# 19_WIFI_BLE.net
KiCad netlist of a schematic drawn in Altium Designer
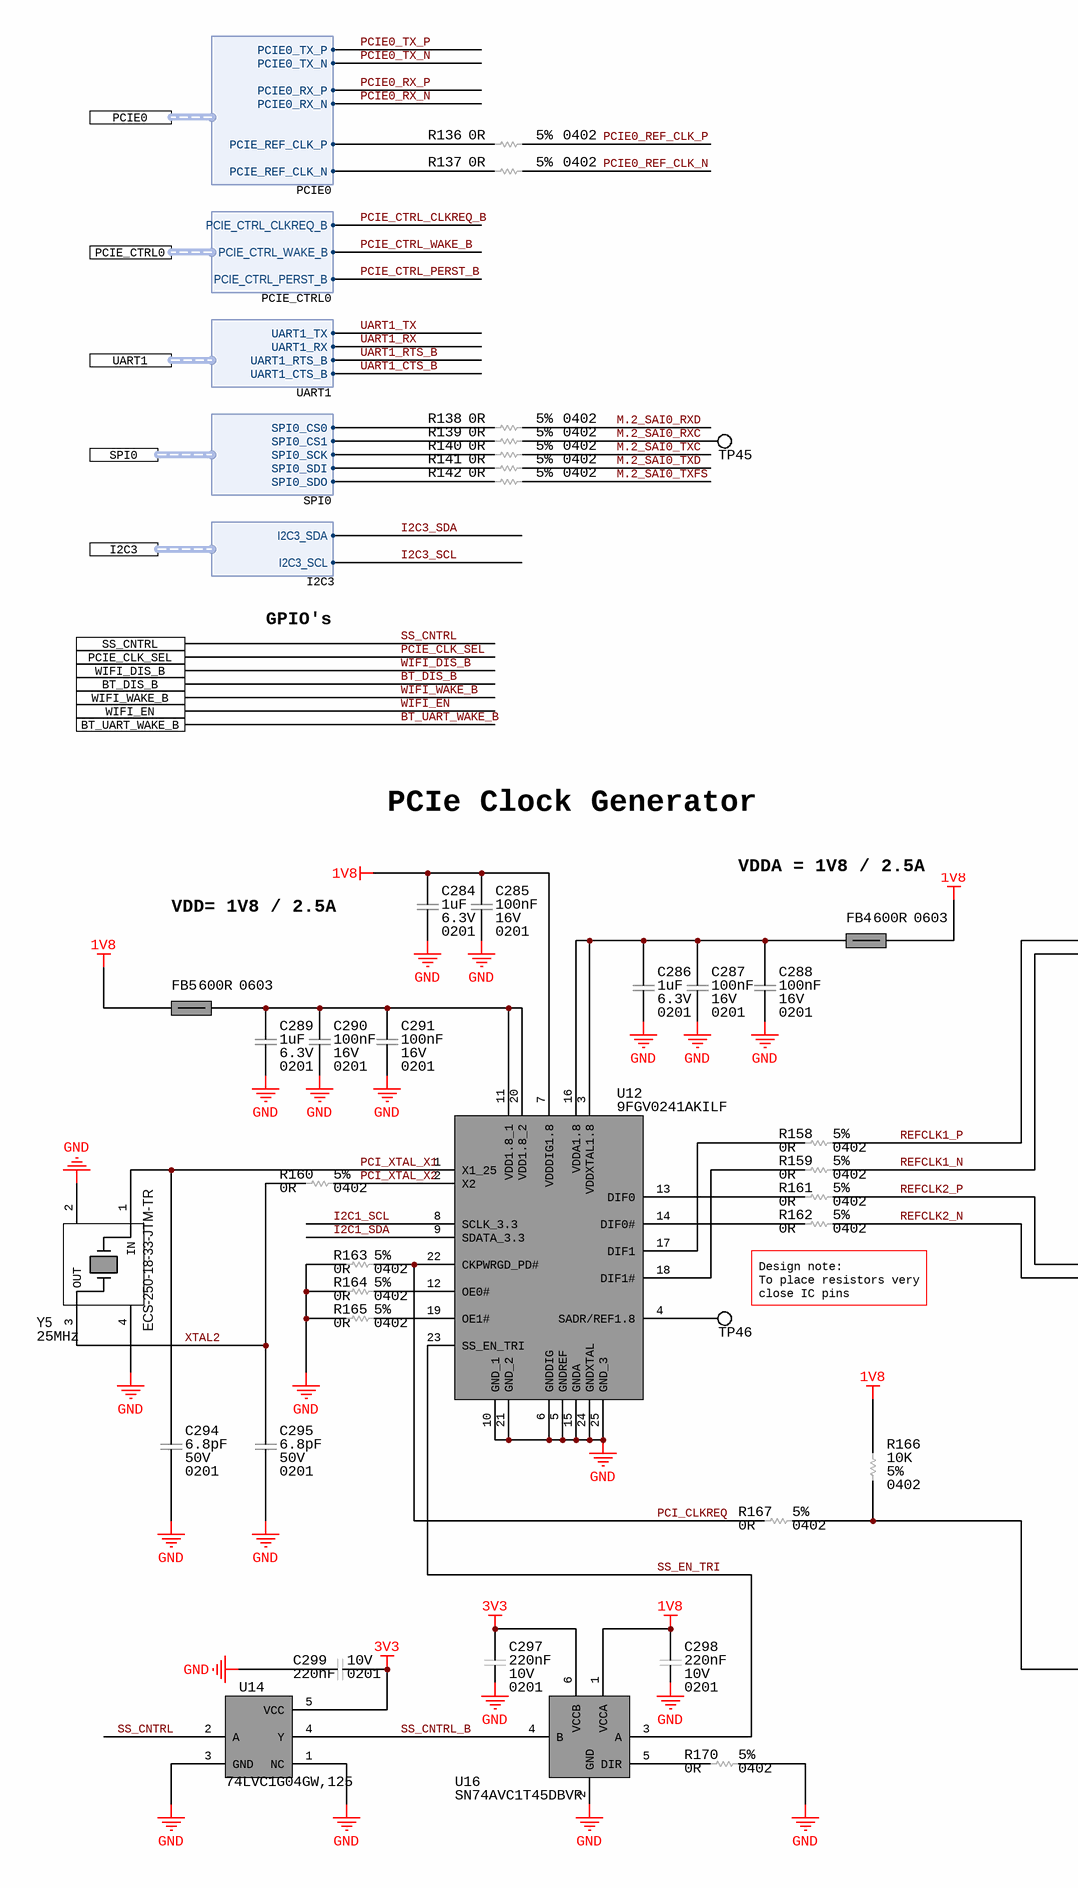
[diagram p0: 19_WIFI_BLE.SchDoc, left]
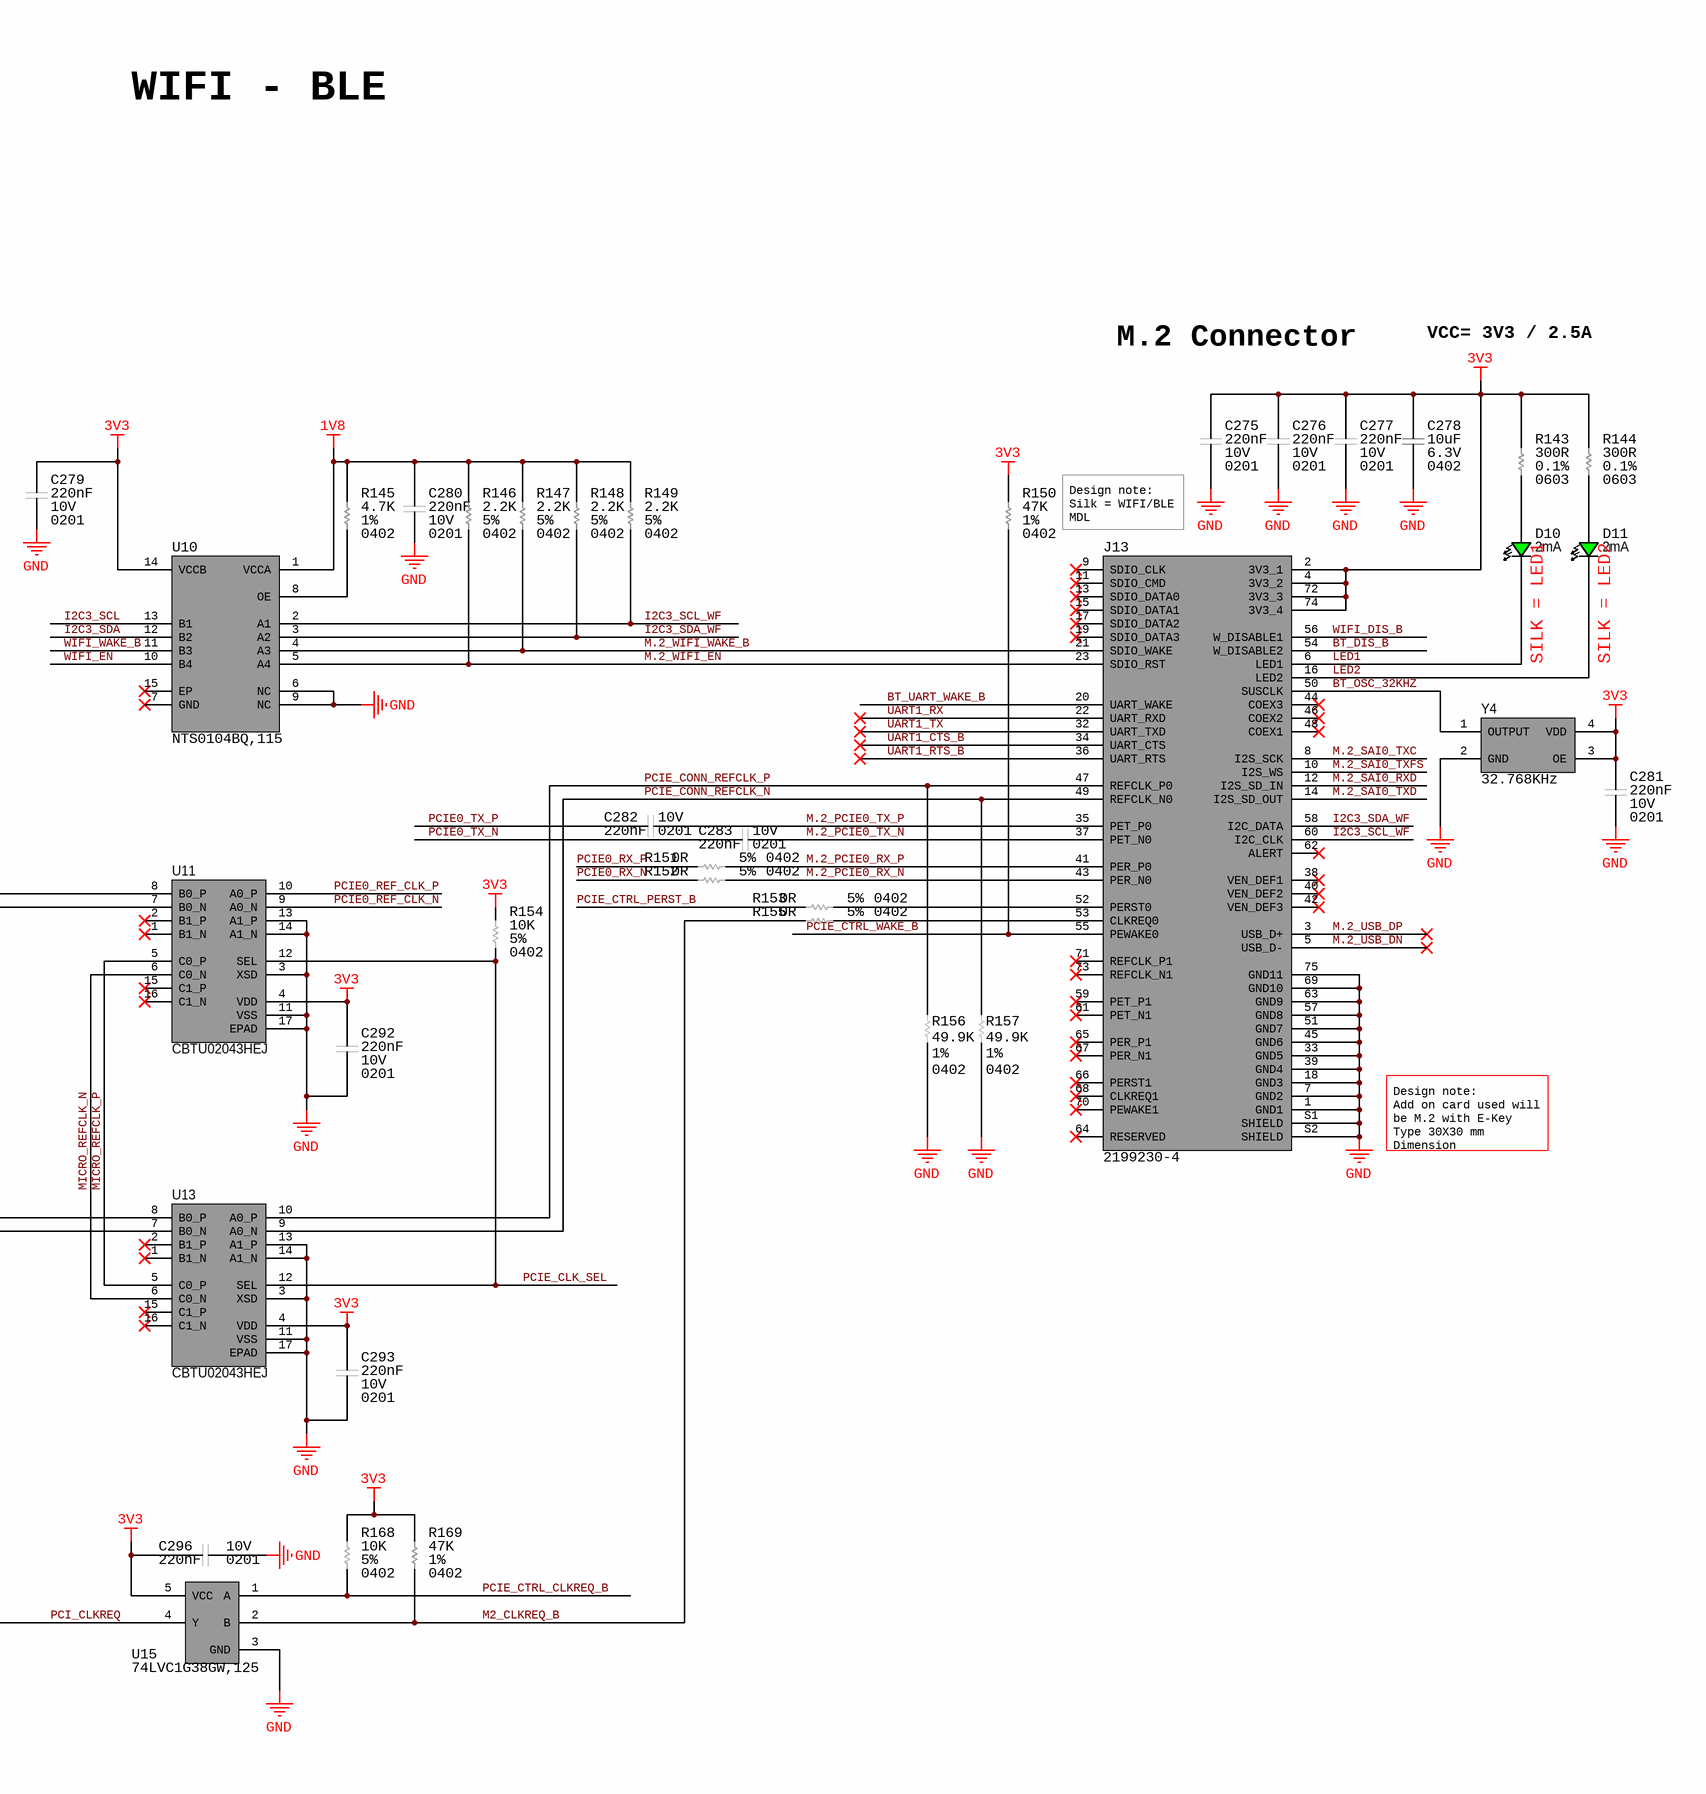
[diagram p1: 19_WIFI_BLE.SchDoc, right]

(export (version "E")
  (design (tool "Eeschema 10.0.6"))
  (components
    (comp (ref "C275")
      (value "LMK063BJ224MP-F")
      (footprint "CAP_0201_CAPC0603X03N")
      (description "Multilayer Ceramic Capacitors (High dielectric type), 10V, 0.22 uF, ± 20 %, 0201, X5R, RoHS")
      (fields
        (field (name "MANUFACTURER") "Taiyo Yuden")
        (field (name "TOLERANCE") "20%")
        (field (name "VOLTAGE RATING (DC)") "10V")
        (field (name "CAPACITANCE") "220nF")
        (field (name "CASE/PACKAGE") "0201")
      )
      (libsource (lib "Electronic Devices_LIB") (part "CAP_0.22UF_10V_X5R_0201"))
    )
    (comp (ref "C276")
      (value "LMK063BJ224MP-F")
      (footprint "CAP_0201_CAPC0603X03N")
      (description "Multilayer Ceramic Capacitors (High dielectric type), 10V, 0.22 uF, ± 20 %, 0201, X5R, RoHS")
      (fields
        (field (name "MANUFACTURER") "Taiyo Yuden")
        (field (name "TOLERANCE") "20%")
        (field (name "VOLTAGE RATING (DC)") "10V")
        (field (name "CAPACITANCE") "220nF")
        (field (name "CASE/PACKAGE") "0201")
      )
      (libsource (lib "Electronic Devices_LIB") (part "CAP_0.22UF_10V_X5R_0201"))
    )
    (comp (ref "C277")
      (value "LMK063BJ224MP-F")
      (footprint "CAP_0201_CAPC0603X03N")
      (description "Multilayer Ceramic Capacitors (High dielectric type), 10V, 0.22 uF, ± 20 %, 0201, X5R, RoHS")
      (fields
        (field (name "MANUFACTURER") "Taiyo Yuden")
        (field (name "TOLERANCE") "20%")
        (field (name "VOLTAGE RATING (DC)") "10V")
        (field (name "CAPACITANCE") "220nF")
        (field (name "CASE/PACKAGE") "0201")
      )
      (libsource (lib "Electronic Devices_LIB") (part "CAP_0.22UF_10V_X5R_0201"))
    )
    (comp (ref "C278")
      (value "CL05A106MQ5NUNC")
      (footprint "CAP_0402_CAPC1005X05N")
      (description "Cap Ceramic 10uF 6.3V X5R 20% SMD 0402 85C T/R")
      (fields
        (field (name "MANUFACTURER") "Samsung")
        (field (name "TOLERANCE") "20%")
        (field (name "CASE/PACKAGE") "0402")
        (field (name "CAPACITANCE") "10uF")
        (field (name "VOLTAGE RATING") "6.3V")
      )
      (libsource (lib "Electronic Devices_LIB") (part "CAP_10UF_6.3V_X5R_0402"))
    )
    (comp (ref "C279")
      (value "LMK063BJ224MP-F")
      (footprint "CAP_0201_CAPC0603X03N")
      (description "Multilayer Ceramic Capacitors (High dielectric type), 10V, 0.22 uF, ± 20 %, 0201, X5R, RoHS")
      (fields
        (field (name "MANUFACTURER") "Taiyo Yuden")
        (field (name "TOLERANCE") "20%")
        (field (name "VOLTAGE RATING (DC)") "10V")
        (field (name "CAPACITANCE") "220nF")
        (field (name "CASE/PACKAGE") "0201")
      )
      (libsource (lib "Electronic Devices_LIB") (part "CAP_0.22UF_10V_X5R_0201"))
    )
    (comp (ref "C280")
      (value "LMK063BJ224MP-F")
      (footprint "CAP_0201_CAPC0603X03N")
      (description "Multilayer Ceramic Capacitors (High dielectric type), 10V, 0.22 uF, ± 20 %, 0201, X5R, RoHS")
      (fields
        (field (name "MANUFACTURER") "Taiyo Yuden")
        (field (name "TOLERANCE") "20%")
        (field (name "VOLTAGE RATING (DC)") "10V")
        (field (name "CAPACITANCE") "220nF")
        (field (name "CASE/PACKAGE") "0201")
      )
      (libsource (lib "Electronic Devices_LIB") (part "CAP_0.22UF_10V_X5R_0201"))
    )
    (comp (ref "C281")
      (value "LMK063BJ224MP-F")
      (footprint "CAP_0201_CAPC0603X03N")
      (description "Multilayer Ceramic Capacitors (High dielectric type), 10V, 0.22 uF, ± 20 %, 0201, X5R, RoHS")
      (fields
        (field (name "MANUFACTURER") "Taiyo Yuden")
        (field (name "TOLERANCE") "20%")
        (field (name "VOLTAGE RATING (DC)") "10V")
        (field (name "CAPACITANCE") "220nF")
        (field (name "CASE/PACKAGE") "0201")
      )
      (libsource (lib "Electronic Devices_LIB") (part "CAP_0.22UF_10V_X5R_0201"))
    )
    (comp (ref "C282")
      (value "LMK063BJ224MP-F")
      (footprint "CAP_0201_CAPC0603X03N")
      (description "Multilayer Ceramic Capacitors (High dielectric type), 10V, 0.22 uF, ± 20 %, 0201, X5R, RoHS")
      (fields
        (field (name "MANUFACTURER") "Taiyo Yuden")
        (field (name "TOLERANCE") "20%")
        (field (name "VOLTAGE RATING (DC)") "10V")
        (field (name "CAPACITANCE") "220nF")
        (field (name "CASE/PACKAGE") "0201")
      )
      (libsource (lib "Electronic Devices_LIB") (part "CAP_0.22UF_10V_X5R_0201"))
    )
    (comp (ref "C283")
      (value "LMK063BJ224MP-F")
      (footprint "CAP_0201_CAPC0603X03N")
      (description "Multilayer Ceramic Capacitors (High dielectric type), 10V, 0.22 uF, ± 20 %, 0201, X5R, RoHS")
      (fields
        (field (name "MANUFACTURER") "Taiyo Yuden")
        (field (name "TOLERANCE") "20%")
        (field (name "VOLTAGE RATING (DC)") "10V")
        (field (name "CAPACITANCE") "220nF")
        (field (name "CASE/PACKAGE") "0201")
      )
      (libsource (lib "Electronic Devices_LIB") (part "CAP_0.22UF_10V_X5R_0201"))
    )
    (comp (ref "C284")
      (value "02016D105MAT2A")
      (footprint "CAP_0201_CAPC0603X03N")
      (description "0201 1 uF 6.3 V ±20 % Tolerance X5R Surface Mount Multilayer Ceramic Capacitor")
      (fields
        (field (name "MANUFACTURER") "Kyocera AVX")
        (field (name "TOLERANCE") "20%")
        (field (name "VOLTAGE RATING (DC)") "6.3V")
        (field (name "CAPACITANCE") "1uF")
        (field (name "CASE/PACKAGE") "0201")
      )
      (libsource (lib "Electronic Devices_LIB") (part "CAP_1UF_6.3V_X5R_0201"))
    )
    (comp (ref "C285")
      (value "GRM033C71C104KE14D")
      (footprint "CAP_0201_CAPC0603X03N")
      (description "Multilayer Ceramic Capacitor, 0.1 uF, 16 V, ± 10%, X7S, 0201 [0603 Metric]")
      (fields
        (field (name "MANUFACTURER") "Murata")
        (field (name "TOLERANCE") "10%")
        (field (name "VOLTAGE RATING") "16V")
        (field (name "CAPACITANCE") "100nF")
        (field (name "CASE/PACKAGE") "0201")
      )
      (libsource (lib "Electronic Devices_LIB") (part "CAP_100nF_16V_X7S_0201"))
    )
    (comp (ref "C286")
      (value "02016D105MAT2A")
      (footprint "CAP_0201_CAPC0603X03N")
      (description "0201 1 uF 6.3 V ±20 % Tolerance X5R Surface Mount Multilayer Ceramic Capacitor")
      (fields
        (field (name "MANUFACTURER") "Kyocera AVX")
        (field (name "TOLERANCE") "20%")
        (field (name "VOLTAGE RATING (DC)") "6.3V")
        (field (name "CAPACITANCE") "1uF")
        (field (name "CASE/PACKAGE") "0201")
      )
      (libsource (lib "Electronic Devices_LIB") (part "CAP_1UF_6.3V_X5R_0201"))
    )
    (comp (ref "C287")
      (value "GRM033C71C104KE14D")
      (footprint "CAP_0201_CAPC0603X03N")
      (description "Multilayer Ceramic Capacitor, 0.1 uF, 16 V, ± 10%, X7S, 0201 [0603 Metric]")
      (fields
        (field (name "MANUFACTURER") "Murata")
        (field (name "TOLERANCE") "10%")
        (field (name "VOLTAGE RATING") "16V")
        (field (name "CAPACITANCE") "100nF")
        (field (name "CASE/PACKAGE") "0201")
      )
      (libsource (lib "Electronic Devices_LIB") (part "CAP_100nF_16V_X7S_0201"))
    )
    (comp (ref "C288")
      (value "GRM033C71C104KE14D")
      (footprint "CAP_0201_CAPC0603X03N")
      (description "Multilayer Ceramic Capacitor, 0.1 uF, 16 V, ± 10%, X7S, 0201 [0603 Metric]")
      (fields
        (field (name "MANUFACTURER") "Murata")
        (field (name "TOLERANCE") "10%")
        (field (name "VOLTAGE RATING") "16V")
        (field (name "CAPACITANCE") "100nF")
        (field (name "CASE/PACKAGE") "0201")
      )
      (libsource (lib "Electronic Devices_LIB") (part "CAP_100nF_16V_X7S_0201"))
    )
    (comp (ref "C289")
      (value "02016D105MAT2A")
      (footprint "CAP_0201_CAPC0603X03N")
      (description "0201 1 uF 6.3 V ±20 % Tolerance X5R Surface Mount Multilayer Ceramic Capacitor")
      (fields
        (field (name "MANUFACTURER") "Kyocera AVX")
        (field (name "TOLERANCE") "20%")
        (field (name "VOLTAGE RATING (DC)") "6.3V")
        (field (name "CAPACITANCE") "1uF")
        (field (name "CASE/PACKAGE") "0201")
      )
      (libsource (lib "Electronic Devices_LIB") (part "CAP_1UF_6.3V_X5R_0201"))
    )
    (comp (ref "C290")
      (value "GRM033C71C104KE14D")
      (footprint "CAP_0201_CAPC0603X03N")
      (description "Multilayer Ceramic Capacitor, 0.1 uF, 16 V, ± 10%, X7S, 0201 [0603 Metric]")
      (fields
        (field (name "MANUFACTURER") "Murata")
        (field (name "TOLERANCE") "10%")
        (field (name "VOLTAGE RATING") "16V")
        (field (name "CAPACITANCE") "100nF")
        (field (name "CASE/PACKAGE") "0201")
      )
      (libsource (lib "Electronic Devices_LIB") (part "CAP_100nF_16V_X7S_0201"))
    )
    (comp (ref "C291")
      (value "GRM033C71C104KE14D")
      (footprint "CAP_0201_CAPC0603X03N")
      (description "Multilayer Ceramic Capacitor, 0.1 uF, 16 V, ± 10%, X7S, 0201 [0603 Metric]")
      (fields
        (field (name "MANUFACTURER") "Murata")
        (field (name "TOLERANCE") "10%")
        (field (name "VOLTAGE RATING") "16V")
        (field (name "CAPACITANCE") "100nF")
        (field (name "CASE/PACKAGE") "0201")
      )
      (libsource (lib "Electronic Devices_LIB") (part "CAP_100nF_16V_X7S_0201"))
    )
    (comp (ref "C292")
      (value "LMK063BJ224MP-F")
      (footprint "CAP_0201_CAPC0603X03N")
      (description "Multilayer Ceramic Capacitors (High dielectric type), 10V, 0.22 uF, ± 20 %, 0201, X5R, RoHS")
      (fields
        (field (name "MANUFACTURER") "Taiyo Yuden")
        (field (name "TOLERANCE") "20%")
        (field (name "VOLTAGE RATING (DC)") "10V")
        (field (name "CAPACITANCE") "220nF")
        (field (name "CASE/PACKAGE") "0201")
      )
      (libsource (lib "Electronic Devices_LIB") (part "CAP_0.22UF_10V_X5R_0201"))
    )
    (comp (ref "C293")
      (value "LMK063BJ224MP-F")
      (footprint "CAP_0201_CAPC0603X03N")
      (description "Multilayer Ceramic Capacitors (High dielectric type), 10V, 0.22 uF, ± 20 %, 0201, X5R, RoHS")
      (fields
        (field (name "MANUFACTURER") "Taiyo Yuden")
        (field (name "TOLERANCE") "20%")
        (field (name "VOLTAGE RATING (DC)") "10V")
        (field (name "CAPACITANCE") "220nF")
        (field (name "CASE/PACKAGE") "0201")
      )
      (libsource (lib "Electronic Devices_LIB") (part "CAP_0.22UF_10V_X5R_0201"))
    )
    (comp (ref "C294")
      (value "GRM0335C1H6R8BA01D")
      (footprint "CAP_0201_CAPC0603X03N")
      (description "Cap Ceramic 6.8pF 50V C0G 0.1pF Pad SMD 0201 125C T/R")
      (fields
        (field (name "MANUFACTURER") "Murata")
        (field (name "CAPACITANCE") "6.8pF")
        (field (name "VOLTAGE RATING") "50V")
        (field (name "CASE/PACKAGE") "0201")
      )
      (libsource (lib "Electronic Devices_LIB") (part "CAP_6.8pF_50V_NP0_0201"))
    )
    (comp (ref "C295")
      (value "GRM0335C1H6R8BA01D")
      (footprint "CAP_0201_CAPC0603X03N")
      (description "Cap Ceramic 6.8pF 50V C0G 0.1pF Pad SMD 0201 125C T/R")
      (fields
        (field (name "MANUFACTURER") "Murata")
        (field (name "CAPACITANCE") "6.8pF")
        (field (name "VOLTAGE RATING") "50V")
        (field (name "CASE/PACKAGE") "0201")
      )
      (libsource (lib "Electronic Devices_LIB") (part "CAP_6.8pF_50V_NP0_0201"))
    )
    (comp (ref "C296")
      (value "LMK063BJ224MP-F")
      (footprint "CAP_0201_CAPC0603X03N")
      (description "Multilayer Ceramic Capacitors (High dielectric type), 10V, 0.22 uF, ± 20 %, 0201, X5R, RoHS")
      (fields
        (field (name "MANUFACTURER") "Taiyo Yuden")
        (field (name "TOLERANCE") "20%")
        (field (name "VOLTAGE RATING (DC)") "10V")
        (field (name "CAPACITANCE") "220nF")
        (field (name "CASE/PACKAGE") "0201")
      )
      (libsource (lib "Electronic Devices_LIB") (part "CAP_0.22UF_10V_X5R_0201"))
    )
    (comp (ref "C297")
      (value "LMK063BJ224MP-F")
      (footprint "CAP_0201_CAPC0603X03N")
      (description "Multilayer Ceramic Capacitors (High dielectric type), 10V, 0.22 uF, ± 20 %, 0201, X5R, RoHS")
      (fields
        (field (name "MANUFACTURER") "Taiyo Yuden")
        (field (name "TOLERANCE") "20%")
        (field (name "VOLTAGE RATING (DC)") "10V")
        (field (name "CAPACITANCE") "220nF")
        (field (name "CASE/PACKAGE") "0201")
      )
      (libsource (lib "Electronic Devices_LIB") (part "CAP_0.22UF_10V_X5R_0201"))
    )
    (comp (ref "C298")
      (value "LMK063BJ224MP-F")
      (footprint "CAP_0201_CAPC0603X03N")
      (description "Multilayer Ceramic Capacitors (High dielectric type), 10V, 0.22 uF, ± 20 %, 0201, X5R, RoHS")
      (fields
        (field (name "MANUFACTURER") "Taiyo Yuden")
        (field (name "TOLERANCE") "20%")
        (field (name "VOLTAGE RATING (DC)") "10V")
        (field (name "CAPACITANCE") "220nF")
        (field (name "CASE/PACKAGE") "0201")
      )
      (libsource (lib "Electronic Devices_LIB") (part "CAP_0.22UF_10V_X5R_0201"))
    )
    (comp (ref "C299")
      (value "LMK063BJ224MP-F")
      (footprint "CAP_0201_CAPC0603X03N")
      (description "Multilayer Ceramic Capacitors (High dielectric type), 10V, 0.22 uF, ± 20 %, 0201, X5R, RoHS")
      (fields
        (field (name "MANUFACTURER") "Taiyo Yuden")
        (field (name "TOLERANCE") "20%")
        (field (name "VOLTAGE RATING (DC)") "10V")
        (field (name "CAPACITANCE") "220nF")
        (field (name "CASE/PACKAGE") "0201")
      )
      (libsource (lib "Electronic Devices_LIB") (part "CAP_0.22UF_10V_X5R_0201"))
    )
    (comp (ref "D10")
      (value "APDA3020LZGCK")
      (footprint "LED_GREEN_APDA3020LZGCK")
      (description "LED GREEN CLEAR 2SMD R/A  1500mcd")
      (fields (field (name "MANUFACTURER") "Kingbright") (field (name "TEST CURRENT") "2mA"))
      (libsource (lib "Electronic Devices_LIB") (part "LED_DIO_GREEN_2mA_APDA3020LZGCK"))
    )
    (comp (ref "D11")
      (value "APDA3020LZGCK")
      (footprint "LED_GREEN_APDA3020LZGCK")
      (description "LED GREEN CLEAR 2SMD R/A  1500mcd")
      (fields (field (name "MANUFACTURER") "Kingbright") (field (name "TEST CURRENT") "2mA"))
      (libsource (lib "Electronic Devices_LIB") (part "LED_DIO_GREEN_2mA_APDA3020LZGCK"))
    )
    (comp (ref "FB4")
      (value "742792653")
      (footprint "IND_0603_INDC1608X08N")
      (description "Chip NTC Thermistors (Sensor), Resistance (at 25°C)=10kΩ, Resistance Tolerance (at 25°C)=±1%")
      (fields
        (field (name "MANUFACTURER") "Wurth Electronics")
        (field (name "TOLERANCE") "25%")
        (field (name "IMPEDANCE") "600R")
        (field (name "CASE CODE (IMPERIAL)") "0603")
      )
      (libsource (lib "Electronic Devices_LIB") (part "IND_FERRITE_BEADS_600R_300mA_0603_742792653"))
    )
    (comp (ref "FB5")
      (value "742792653")
      (footprint "IND_0603_INDC1608X08N")
      (description "Chip NTC Thermistors (Sensor), Resistance (at 25°C)=10kΩ, Resistance Tolerance (at 25°C)=±1%")
      (fields
        (field (name "MANUFACTURER") "Wurth Electronics")
        (field (name "TOLERANCE") "25%")
        (field (name "IMPEDANCE") "600R")
        (field (name "CASE CODE (IMPERIAL)") "0603")
      )
      (libsource (lib "Electronic Devices_LIB") (part "IND_FERRITE_BEADS_600R_300mA_0603_742792653"))
    )
    (comp (ref "J13")
      (value "2199230-4")
      (footprint "TE_21992304")
      (description "CONNECTOR, BACKPLANE, HOUSING, RCPT, 67POS, 2ROW; Connector Type: Card Edge; Seri")
      (fields (field (name "MANUFACTURER") "TE Connectivity"))
      (libsource (lib "Electronic Devices_LIB") (part "CONN_M.2_FEMALE_2199230-4"))
    )
    (comp (ref "R136")
      (value "ERJ-2GE0R00X")
      (footprint "RES_0402_RESC1005X04N")
      (description "SMD Chip Resistor, Jumper, 0 ohm, 100 mW, 0402 [1005 Metric], Thick Film, General Purpose")
      (fields
        (field (name "MANUFACTURER") "Panasonic")
        (field (name "CASE CODE (IMPERIAL)") "0402")
        (field (name "TOLERANCE") "5%")
        (field (name "RESISTANCE") "0R")
      )
      (libsource (lib "Electronic Devices_LIB") (part "RES_0R_5%_100mW_0402"))
    )
    (comp (ref "R137")
      (value "ERJ-2GE0R00X")
      (footprint "RES_0402_RESC1005X04N")
      (description "SMD Chip Resistor, Jumper, 0 ohm, 100 mW, 0402 [1005 Metric], Thick Film, General Purpose")
      (fields
        (field (name "MANUFACTURER") "Panasonic")
        (field (name "CASE CODE (IMPERIAL)") "0402")
        (field (name "TOLERANCE") "5%")
        (field (name "RESISTANCE") "0R")
      )
      (libsource (lib "Electronic Devices_LIB") (part "RES_0R_5%_100mW_0402"))
    )
    (comp (ref "R138")
      (value "ERJ-2GE0R00X")
      (footprint "RES_0402_RESC1005X04N")
      (description "SMD Chip Resistor, Jumper, 0 ohm, 100 mW, 0402 [1005 Metric], Thick Film, General Purpose")
      (fields
        (field (name "MANUFACTURER") "Panasonic")
        (field (name "CASE CODE (IMPERIAL)") "0402")
        (field (name "TOLERANCE") "5%")
        (field (name "RESISTANCE") "0R")
      )
      (libsource (lib "Electronic Devices_LIB") (part "RES_0R_5%_100mW_0402"))
    )
    (comp (ref "R139")
      (value "ERJ-2GE0R00X")
      (footprint "RES_0402_RESC1005X04N")
      (description "SMD Chip Resistor, Jumper, 0 ohm, 100 mW, 0402 [1005 Metric], Thick Film, General Purpose")
      (fields
        (field (name "MANUFACTURER") "Panasonic")
        (field (name "CASE CODE (IMPERIAL)") "0402")
        (field (name "TOLERANCE") "5%")
        (field (name "RESISTANCE") "0R")
      )
      (libsource (lib "Electronic Devices_LIB") (part "RES_0R_5%_100mW_0402"))
    )
    (comp (ref "R140")
      (value "ERJ-2GE0R00X")
      (footprint "RES_0402_RESC1005X04N")
      (description "SMD Chip Resistor, Jumper, 0 ohm, 100 mW, 0402 [1005 Metric], Thick Film, General Purpose")
      (fields
        (field (name "MANUFACTURER") "Panasonic")
        (field (name "CASE CODE (IMPERIAL)") "0402")
        (field (name "TOLERANCE") "5%")
        (field (name "RESISTANCE") "0R")
      )
      (libsource (lib "Electronic Devices_LIB") (part "RES_0R_5%_100mW_0402"))
    )
    (comp (ref "R141")
      (value "ERJ-2GE0R00X")
      (footprint "RES_0402_RESC1005X04N")
      (description "SMD Chip Resistor, Jumper, 0 ohm, 100 mW, 0402 [1005 Metric], Thick Film, General Purpose")
      (fields
        (field (name "MANUFACTURER") "Panasonic")
        (field (name "CASE CODE (IMPERIAL)") "0402")
        (field (name "TOLERANCE") "5%")
        (field (name "RESISTANCE") "0R")
      )
      (libsource (lib "Electronic Devices_LIB") (part "RES_0R_5%_100mW_0402"))
    )
    (comp (ref "R142")
      (value "ERJ-2GE0R00X")
      (footprint "RES_0402_RESC1005X04N")
      (description "SMD Chip Resistor, Jumper, 0 ohm, 100 mW, 0402 [1005 Metric], Thick Film, General Purpose")
      (fields
        (field (name "MANUFACTURER") "Panasonic")
        (field (name "CASE CODE (IMPERIAL)") "0402")
        (field (name "TOLERANCE") "5%")
        (field (name "RESISTANCE") "0R")
      )
      (libsource (lib "Electronic Devices_LIB") (part "RES_0R_5%_100mW_0402"))
    )
    (comp (ref "R143")
      (value "RT0603BRD07300RL")
      (footprint "RES_0603_RESC1608X04N")
      (description "Res Thin Film 0603 300 Ohm 0.1% 0.1W(1/10W) ±25ppm/C Pad SMD T/R")
      (fields
        (field (name "MANUFACTURER") "Yageo")
        (field (name "CASE CODE (IMPERIAL)") "0603")
        (field (name "TOLERANCE") "0.1%")
        (field (name "RESISTANCE") "300R")
      )
      (libsource (lib "Electronic Devices_LIB") (part "RES_300R_0.1%_100mW_0603"))
    )
    (comp (ref "R144")
      (value "RT0603BRD07300RL")
      (footprint "RES_0603_RESC1608X04N")
      (description "Res Thin Film 0603 300 Ohm 0.1% 0.1W(1/10W) ±25ppm/C Pad SMD T/R")
      (fields
        (field (name "MANUFACTURER") "Yageo")
        (field (name "CASE CODE (IMPERIAL)") "0603")
        (field (name "TOLERANCE") "0.1%")
        (field (name "RESISTANCE") "300R")
      )
      (libsource (lib "Electronic Devices_LIB") (part "RES_300R_0.1%_100mW_0603"))
    )
    (comp (ref "R145")
      (value "ERJ-2RKF4701X")
      (footprint "RES_0402_RESC1005X04N")
      (description "Res Thick Film 0402 4.7K Ohm 1% 0.1W ±100ppm/°C Molded SMD Punched Carrier T/R")
      (fields
        (field (name "MANUFACTURER") "Panasonic")
        (field (name "TOLERANCE") "1%")
        (field (name "CASE CODE (IMPERIAL)") "0402")
        (field (name "RESISTANCE") "4.7K")
      )
      (libsource (lib "Electronic Devices_LIB") (part "RES_4.7K_1%_100mW_0402"))
    )
    (comp (ref "R146")
      (value "RC0402JR-072K2L")
      (footprint "RES_0402_RESC1005X04N")
      (description "SMD Chip Resistor, 2.2 kOhm, ± 5%, 63 mW, 0402 [1005 Metric], Thick Film, General Purpose")
      (fields
        (field (name "MANUFACTURER") "Yageo")
        (field (name "TOLERANCE") "5%")
        (field (name "RESISTANCE") "2.2K")
        (field (name "CASE/PACKAGE") "0402")
      )
      (libsource (lib "Electronic Devices_LIB") (part "RES_2.2K_5%_63mW_0402"))
    )
    (comp (ref "R147")
      (value "RC0402JR-072K2L")
      (footprint "RES_0402_RESC1005X04N")
      (description "SMD Chip Resistor, 2.2 kOhm, ± 5%, 63 mW, 0402 [1005 Metric], Thick Film, General Purpose")
      (fields
        (field (name "MANUFACTURER") "Yageo")
        (field (name "TOLERANCE") "5%")
        (field (name "RESISTANCE") "2.2K")
        (field (name "CASE/PACKAGE") "0402")
      )
      (libsource (lib "Electronic Devices_LIB") (part "RES_2.2K_5%_63mW_0402"))
    )
    (comp (ref "R148")
      (value "RC0402JR-072K2L")
      (footprint "RES_0402_RESC1005X04N")
      (description "SMD Chip Resistor, 2.2 kOhm, ± 5%, 63 mW, 0402 [1005 Metric], Thick Film, General Purpose")
      (fields
        (field (name "MANUFACTURER") "Yageo")
        (field (name "TOLERANCE") "5%")
        (field (name "RESISTANCE") "2.2K")
        (field (name "CASE/PACKAGE") "0402")
      )
      (libsource (lib "Electronic Devices_LIB") (part "RES_2.2K_5%_63mW_0402"))
    )
    (comp (ref "R149")
      (value "RC0402JR-072K2L")
      (footprint "RES_0402_RESC1005X04N")
      (description "SMD Chip Resistor, 2.2 kOhm, ± 5%, 63 mW, 0402 [1005 Metric], Thick Film, General Purpose")
      (fields
        (field (name "MANUFACTURER") "Yageo")
        (field (name "TOLERANCE") "5%")
        (field (name "RESISTANCE") "2.2K")
        (field (name "CASE/PACKAGE") "0402")
      )
      (libsource (lib "Electronic Devices_LIB") (part "RES_2.2K_5%_63mW_0402"))
    )
    (comp (ref "R150")
      (value "ERJ-2RKF4702X")
      (footprint "RES_0402_RESC1005X04N")
      (description "Res Thick Film 0402 47K Ohm 1% 0.1W ±100ppm/°C Molded SMD Punched Carrier T/R")
      (fields
        (field (name "MANUFACTURER") "Panasonic")
        (field (name "TOLERANCE") "1%")
        (field (name "RESISTANCE") "47K")
        (field (name "CASE/PACKAGE") "0402")
      )
      (libsource (lib "Electronic Devices_LIB") (part "RES_47K_1%_100MW_0402"))
    )
    (comp (ref "R151")
      (value "ERJ-2GE0R00X")
      (footprint "RES_0402_RESC1005X04N")
      (description "SMD Chip Resistor, Jumper, 0 ohm, 100 mW, 0402 [1005 Metric], Thick Film, General Purpose")
      (fields
        (field (name "MANUFACTURER") "Panasonic")
        (field (name "CASE CODE (IMPERIAL)") "0402")
        (field (name "TOLERANCE") "5%")
        (field (name "RESISTANCE") "0R")
      )
      (libsource (lib "Electronic Devices_LIB") (part "RES_0R_5%_100mW_0402"))
    )
    (comp (ref "R152")
      (value "ERJ-2GE0R00X")
      (footprint "RES_0402_RESC1005X04N")
      (description "SMD Chip Resistor, Jumper, 0 ohm, 100 mW, 0402 [1005 Metric], Thick Film, General Purpose")
      (fields
        (field (name "MANUFACTURER") "Panasonic")
        (field (name "CASE CODE (IMPERIAL)") "0402")
        (field (name "TOLERANCE") "5%")
        (field (name "RESISTANCE") "0R")
      )
      (libsource (lib "Electronic Devices_LIB") (part "RES_0R_5%_100mW_0402"))
    )
    (comp (ref "R153")
      (value "ERJ-2GE0R00X")
      (footprint "RES_0402_RESC1005X04N")
      (description "SMD Chip Resistor, Jumper, 0 ohm, 100 mW, 0402 [1005 Metric], Thick Film, General Purpose")
      (fields
        (field (name "MANUFACTURER") "Panasonic")
        (field (name "CASE CODE (IMPERIAL)") "0402")
        (field (name "TOLERANCE") "5%")
        (field (name "RESISTANCE") "0R")
      )
      (libsource (lib "Electronic Devices_LIB") (part "RES_0R_5%_100mW_0402"))
    )
    (comp (ref "R154")
      (value "ERJ-2GEJ103X")
      (footprint "RES_0402_RESC1005X04N")
      (description "Res Thick Film 0402 10K Ohm 5% 1/10W ±200ppm/°C Molded SMD Punched Carrier T/R")
      (fields
        (field (name "MANUFACTURER") "Panasonic")
        (field (name "TOLERANCE") "5%")
        (field (name "RESISTANCE") "10K")
        (field (name "CASE/PACKAGE") "0402")
      )
      (libsource (lib "Electronic Devices_LIB") (part "RES_10K_5%_100mW_0402"))
    )
    (comp (ref "R155")
      (value "ERJ-2GE0R00X")
      (footprint "RES_0402_RESC1005X04N")
      (description "SMD Chip Resistor, Jumper, 0 ohm, 100 mW, 0402 [1005 Metric], Thick Film, General Purpose")
      (fields
        (field (name "MANUFACTURER") "Panasonic")
        (field (name "CASE CODE (IMPERIAL)") "0402")
        (field (name "TOLERANCE") "5%")
        (field (name "RESISTANCE") "0R")
      )
      (libsource (lib "Electronic Devices_LIB") (part "RES_0R_5%_100mW_0402"))
    )
    (comp (ref "R156")
      (value "CRCW040249K9FKED")
      (footprint "RES_0402_RESC1005X04N")
      (description "Res Thick Film 0402 49.9K Ohm 1% 1/16W ±100ppm/°C Molded SMD SMD Paper T/R")
      (fields
        (field (name "MANUFACTURER") "Vishay")
        (field (name "RESISTANCE") "49.9K")
        (field (name "TOLERANCE") "1%")
        (field (name "CASE/PACKAGE") "0402")
      )
      (libsource (lib "Electronic Devices_LIB") (part "RES_49.9K_1%_0.0625W_0402"))
    )
    (comp (ref "R157")
      (value "CRCW040249K9FKED")
      (footprint "RES_0402_RESC1005X04N")
      (description "Res Thick Film 0402 49.9K Ohm 1% 1/16W ±100ppm/°C Molded SMD SMD Paper T/R")
      (fields
        (field (name "MANUFACTURER") "Vishay")
        (field (name "RESISTANCE") "49.9K")
        (field (name "TOLERANCE") "1%")
        (field (name "CASE/PACKAGE") "0402")
      )
      (libsource (lib "Electronic Devices_LIB") (part "RES_49.9K_1%_0.0625W_0402"))
    )
    (comp (ref "R158")
      (value "ERJ-2GE0R00X")
      (footprint "RES_0402_RESC1005X04N")
      (description "SMD Chip Resistor, Jumper, 0 ohm, 100 mW, 0402 [1005 Metric], Thick Film, General Purpose")
      (fields
        (field (name "MANUFACTURER") "Panasonic")
        (field (name "CASE CODE (IMPERIAL)") "0402")
        (field (name "TOLERANCE") "5%")
        (field (name "RESISTANCE") "0R")
      )
      (libsource (lib "Electronic Devices_LIB") (part "RES_0R_5%_100mW_0402"))
    )
    (comp (ref "R159")
      (value "ERJ-2GE0R00X")
      (footprint "RES_0402_RESC1005X04N")
      (description "SMD Chip Resistor, Jumper, 0 ohm, 100 mW, 0402 [1005 Metric], Thick Film, General Purpose")
      (fields
        (field (name "MANUFACTURER") "Panasonic")
        (field (name "CASE CODE (IMPERIAL)") "0402")
        (field (name "TOLERANCE") "5%")
        (field (name "RESISTANCE") "0R")
      )
      (libsource (lib "Electronic Devices_LIB") (part "RES_0R_5%_100mW_0402"))
    )
    (comp (ref "R160")
      (value "ERJ-2GE0R00X")
      (footprint "RES_0402_RESC1005X04N")
      (description "SMD Chip Resistor, Jumper, 0 ohm, 100 mW, 0402 [1005 Metric], Thick Film, General Purpose")
      (fields
        (field (name "MANUFACTURER") "Panasonic")
        (field (name "CASE CODE (IMPERIAL)") "0402")
        (field (name "TOLERANCE") "5%")
        (field (name "RESISTANCE") "0R")
      )
      (libsource (lib "Electronic Devices_LIB") (part "RES_0R_5%_100mW_0402"))
    )
    (comp (ref "R161")
      (value "ERJ-2GE0R00X")
      (footprint "RES_0402_RESC1005X04N")
      (description "SMD Chip Resistor, Jumper, 0 ohm, 100 mW, 0402 [1005 Metric], Thick Film, General Purpose")
      (fields
        (field (name "MANUFACTURER") "Panasonic")
        (field (name "CASE CODE (IMPERIAL)") "0402")
        (field (name "TOLERANCE") "5%")
        (field (name "RESISTANCE") "0R")
      )
      (libsource (lib "Electronic Devices_LIB") (part "RES_0R_5%_100mW_0402"))
    )
    (comp (ref "R162")
      (value "ERJ-2GE0R00X")
      (footprint "RES_0402_RESC1005X04N")
      (description "SMD Chip Resistor, Jumper, 0 ohm, 100 mW, 0402 [1005 Metric], Thick Film, General Purpose")
      (fields
        (field (name "MANUFACTURER") "Panasonic")
        (field (name "CASE CODE (IMPERIAL)") "0402")
        (field (name "TOLERANCE") "5%")
        (field (name "RESISTANCE") "0R")
      )
      (libsource (lib "Electronic Devices_LIB") (part "RES_0R_5%_100mW_0402"))
    )
    (comp (ref "R163")
      (value "ERJ-2GE0R00X")
      (footprint "RES_0402_RESC1005X04N")
      (description "SMD Chip Resistor, Jumper, 0 ohm, 100 mW, 0402 [1005 Metric], Thick Film, General Purpose")
      (fields
        (field (name "MANUFACTURER") "Panasonic")
        (field (name "CASE CODE (IMPERIAL)") "0402")
        (field (name "TOLERANCE") "5%")
        (field (name "RESISTANCE") "0R")
      )
      (libsource (lib "Electronic Devices_LIB") (part "RES_0R_5%_100mW_0402"))
    )
    (comp (ref "R164")
      (value "ERJ-2GE0R00X")
      (footprint "RES_0402_RESC1005X04N")
      (description "SMD Chip Resistor, Jumper, 0 ohm, 100 mW, 0402 [1005 Metric], Thick Film, General Purpose")
      (fields
        (field (name "MANUFACTURER") "Panasonic")
        (field (name "CASE CODE (IMPERIAL)") "0402")
        (field (name "TOLERANCE") "5%")
        (field (name "RESISTANCE") "0R")
      )
      (libsource (lib "Electronic Devices_LIB") (part "RES_0R_5%_100mW_0402"))
    )
    (comp (ref "R165")
      (value "ERJ-2GE0R00X")
      (footprint "RES_0402_RESC1005X04N")
      (description "SMD Chip Resistor, Jumper, 0 ohm, 100 mW, 0402 [1005 Metric], Thick Film, General Purpose")
      (fields
        (field (name "MANUFACTURER") "Panasonic")
        (field (name "CASE CODE (IMPERIAL)") "0402")
        (field (name "TOLERANCE") "5%")
        (field (name "RESISTANCE") "0R")
      )
      (libsource (lib "Electronic Devices_LIB") (part "RES_0R_5%_100mW_0402"))
    )
    (comp (ref "R166")
      (value "ERJ-2GEJ103X")
      (footprint "RES_0402_RESC1005X04N")
      (description "Res Thick Film 0402 10K Ohm 5% 1/10W ±200ppm/°C Molded SMD Punched Carrier T/R")
      (fields
        (field (name "MANUFACTURER") "Panasonic")
        (field (name "TOLERANCE") "5%")
        (field (name "RESISTANCE") "10K")
        (field (name "CASE/PACKAGE") "0402")
      )
      (libsource (lib "Electronic Devices_LIB") (part "RES_10K_5%_100mW_0402"))
    )
    (comp (ref "R167")
      (value "ERJ-2GE0R00X")
      (footprint "RES_0402_RESC1005X04N")
      (description "SMD Chip Resistor, Jumper, 0 ohm, 100 mW, 0402 [1005 Metric], Thick Film, General Purpose")
      (fields
        (field (name "MANUFACTURER") "Panasonic")
        (field (name "CASE CODE (IMPERIAL)") "0402")
        (field (name "TOLERANCE") "5%")
        (field (name "RESISTANCE") "0R")
      )
      (libsource (lib "Electronic Devices_LIB") (part "RES_0R_5%_100mW_0402"))
    )
    (comp (ref "R168")
      (value "ERJ-2GEJ103X")
      (footprint "RES_0402_RESC1005X04N")
      (description "Res Thick Film 0402 10K Ohm 5% 1/10W ±200ppm/°C Molded SMD Punched Carrier T/R")
      (fields
        (field (name "MANUFACTURER") "Panasonic")
        (field (name "TOLERANCE") "5%")
        (field (name "RESISTANCE") "10K")
        (field (name "CASE/PACKAGE") "0402")
      )
      (libsource (lib "Electronic Devices_LIB") (part "RES_10K_5%_100mW_0402"))
    )
    (comp (ref "R169")
      (value "ERJ-2RKF4702X")
      (footprint "RES_0402_RESC1005X04N")
      (description "Res Thick Film 0402 47K Ohm 1% 0.1W ±100ppm/°C Molded SMD Punched Carrier T/R")
      (fields
        (field (name "MANUFACTURER") "Panasonic")
        (field (name "TOLERANCE") "1%")
        (field (name "RESISTANCE") "47K")
        (field (name "CASE/PACKAGE") "0402")
      )
      (libsource (lib "Electronic Devices_LIB") (part "RES_47K_1%_100MW_0402"))
    )
    (comp (ref "R170")
      (value "ERJ-2GE0R00X")
      (footprint "RES_0402_RESC1005X04N")
      (description "SMD Chip Resistor, Jumper, 0 ohm, 100 mW, 0402 [1005 Metric], Thick Film, General Purpose")
      (fields
        (field (name "MANUFACTURER") "Panasonic")
        (field (name "CASE CODE (IMPERIAL)") "0402")
        (field (name "TOLERANCE") "5%")
        (field (name "RESISTANCE") "0R")
      )
      (libsource (lib "Electronic Devices_LIB") (part "RES_0R_5%_100mW_0402"))
    )
    (comp (ref "TP45")
      (value "NO COMPONENT")
      (footprint "TP_PAD_0.5MM_SMD_ROUND")
      (description "Test Point, SMD pad, round, 1.5mm, 1.6mm, 3mm diameter")
      (libsource (lib "Electronic Devices_LIB") (part "TP_PAD_SMD_SMALL"))
    )
    (comp (ref "TP46")
      (value "NO COMPONENT")
      (footprint "TP_PAD_0.5MM_SMD_ROUND")
      (description "Test Point, SMD pad, round, 1.5mm, 1.6mm, 3mm diameter")
      (libsource (lib "Electronic Devices_LIB") (part "TP_PAD_SMD_SMALL"))
    )
    (comp (ref "U10")
      (value "NTS0104BQ,115")
      (footprint "QFN50P300X250X100-15N")
      (description "Voltage Level Translator Bidirectional 1 Circuit 4 Channel 50Mbps 14-DHVQFN (2.5x3)")
      (fields (field (name "MANUFACTURER") "NXP Semiconductors"))
      (libsource (lib "Electronic Devices_LIB") (part "IC_LEVEL_TRASLATE_4CH_NTS0104BQ,115"))
    )
    (comp (ref "U11")
      (value "CBTU02043HEJ")
      (footprint "IC_SW_TYPEC_CBTU02044HEJ")
      (description "USB 3.1 Gen 1 Type C switch / TAPE + REEL REEL 13\" Q1 NDP RoHS Compliant: Yes")
      (fields (field (name "MANUFACTURER") "NXP Semiconductors"))
      (libsource (lib "Electronic Devices_LIB") (part "IC_SWITCH_TYPEC_CBTU02043HEJ"))
    )
    (comp (ref "U12")
      (value "9FGV0241AKILF")
      (footprint "QFN50P400X400X100-25N-D")
      (description "Dual Output 1.8 V Very Low Power PCIE GEN1/2/3 Clock Generator - VFQFPN-24")
      (fields (field (name "MANUFACTURER") "Renesas"))
      (libsource (lib "Electronic Devices_LIB") (part "IC_CLOCK_PCIE_100MHZ_9FGV0241AKILF"))
    )
    (comp (ref "U13")
      (value "CBTU02043HEJ")
      (footprint "IC_SW_TYPEC_CBTU02044HEJ")
      (description "USB 3.1 Gen 1 Type C switch / TAPE + REEL REEL 13\" Q1 NDP RoHS Compliant: Yes")
      (fields (field (name "MANUFACTURER") "NXP Semiconductors"))
      (libsource (lib "Electronic Devices_LIB") (part "IC_SWITCH_TYPEC_CBTU02043HEJ"))
    )
    (comp (ref "U14")
      (value "74LVC1G04GW,125")
      (footprint "SOT65P210X110-5N")
      (description "74LVC Series 5.5 V Surface Mount Single Inverting Buffer - TSSOP-5")
      (fields (field (name "MANUFACTURER") "Nexperia"))
      (libsource (lib "Electronic Devices_LIB") (part "IC_INVERTER_1CH_74LVC1G04GW,125"))
    )
    (comp (ref "U15")
      (value "74LVC1G38GW,125")
      (footprint "SOT65P212X110-5N")
      (description "IC GATE NAND 1CH 2-INP 5-TSSOP")
      (fields (field (name "MANUFACTURER") "Nexperia"))
      (libsource (lib "Electronic Devices_LIB") (part "IC_GATE_NAND_1CH_74LVC1G38GW,125"))
    )
    (comp (ref "U16")
      (value "SN74AVC1T45DBVR")
      (footprint "SOT95P280X145-6N")
      (description "1.2V~3.6V 1 1 1.2V~3.6V 500Mbps SOT-23-6 Translators / Level Shifters ROHS")
      (fields (field (name "MANUFACTURER") "Texas Instruments"))
      (libsource (lib "Electronic Devices_LIB") (part "IC_LEVEL_TRANSLATOR_SN74AVC1T45DBVR"))
    )
    (comp (ref "Y4")
      (value "ASH7KW-32.768kHz-L-T")
      (footprint "CRYSTAL_32.768KHZ_ASH7KW32768kHzLT")
      (description "OSC XO 32.768KHZ CMOS SMD")
      (fields (field (name "MANUFACTURER") "Abracon") (field (name "FREQUENCY") "32.768KHz"))
      (libsource (lib "Electronic Devices_LIB") (part "CRYSTAL_ABRACON_32.768KHZ"))
    )
    (comp (ref "Y5")
      (value "ECS-250-18-33-JTM-TR")
      (footprint "CRYSTAL_ECS-250-18-33-JTM-TR")
      (description "Crystal 25MHz ±20ppm (Tol) ±20ppm (Stability) 18pF FUND 40Ohm 4-Pin Mini-CSMD T/R")
      (fields (field (name "MANUFACTURER") "ECS International") (field (name "FREQUENCY") "25MHz"))
      (libsource (lib "Electronic Devices_LIB") (part "CRYSTAL_ECS_25MHZ_ECS-250-18-33-JTM-TR"))
    )
  )
  (nets
    (net (code "6") (name "/BT_DIS_B") (class "Default")
      (node (ref "J13") (pin "54") (pinfunction "W_DISABLE2_54") (pintype "passive"))
    )
    (net (code "7") (name "/BT_OSC_32KHZ") (class "Default")
      (node (ref "J13") (pin "50") (pinfunction "SUSCLK_50") (pintype "passive"))
      (node (ref "Y4") (pin "1") (pinfunction "OUTPUT_1") (pintype "passive"))
    )
    (net (code "8") (name "/BT_UART_WAKE_B") (class "Default")
      (node (ref "J13") (pin "20") (pinfunction "UART_WAKE_20") (pintype "passive"))
    )
    (net (code "9") (name "/I2C1_SCL") (class "Default")
      (node (ref "U12") (pin "8") (pinfunction "SCLK_3.3_8") (pintype "passive"))
    )
    (net (code "10") (name "/I2C1_SDA") (class "Default")
      (node (ref "U12") (pin "9") (pinfunction "SDATA_3.3_9") (pintype "passive"))
    )
    (net (code "11") (name "/I2C3_SCL") (class "Default")
      (node (ref "U10") (pin "13") (pinfunction "B1_13") (pintype "passive"))
    )
    (net (code "12") (name "/I2C3_SCL_WF") (class "Default")
      (node (ref "J13") (pin "60") (pinfunction "I2C_CLK_60") (pintype "passive"))
      (node (ref "R149") (pin "1") (pinfunction "1_1") (pintype "passive"))
      (node (ref "U10") (pin "2") (pinfunction "A1_2") (pintype "passive"))
    )
    (net (code "13") (name "/I2C3_SDA") (class "Default")
      (node (ref "U10") (pin "12") (pinfunction "B2_12") (pintype "passive"))
    )
    (net (code "14") (name "/I2C3_SDA_WF") (class "Default")
      (node (ref "J13") (pin "58") (pinfunction "I2C_DATA_58") (pintype "passive"))
      (node (ref "R148") (pin "1") (pinfunction "1_1") (pintype "passive"))
      (node (ref "U10") (pin "3") (pinfunction "A2_3") (pintype "passive"))
    )
    (net (code "15") (name "/LED1") (class "Default")
      (node (ref "D10") (pin "1") (pinfunction "C_1") (pintype "passive"))
      (node (ref "J13") (pin "6") (pinfunction "LED1_6") (pintype "passive"))
    )
    (net (code "16") (name "/LED2") (class "Default")
      (node (ref "D11") (pin "1") (pinfunction "C_1") (pintype "passive"))
      (node (ref "J13") (pin "16") (pinfunction "LED2_16") (pintype "passive"))
    )
    (net (code "17") (name "/M.2_PCIE0_RX_N") (class "Default")
      (node (ref "J13") (pin "43") (pinfunction "PER_N0_43") (pintype "passive"))
      (node (ref "R152") (pin "2") (pinfunction "2_2") (pintype "passive"))
    )
    (net (code "18") (name "/M.2_PCIE0_RX_P") (class "Default")
      (node (ref "J13") (pin "41") (pinfunction "PER_P0_41") (pintype "passive"))
      (node (ref "R151") (pin "2") (pinfunction "2_2") (pintype "passive"))
    )
    (net (code "19") (name "/M.2_PCIE0_TX_N") (class "Default")
      (node (ref "C283") (pin "1") (pinfunction "1_1") (pintype "passive"))
      (node (ref "J13") (pin "37") (pinfunction "PET_N0_37") (pintype "passive"))
    )
    (net (code "20") (name "/M.2_PCIE0_TX_P") (class "Default")
      (node (ref "C282") (pin "1") (pinfunction "1_1") (pintype "passive"))
      (node (ref "J13") (pin "35") (pinfunction "PET_P0_35") (pintype "passive"))
    )
    (net (code "21") (name "/M.2_SAI0_RXC") (class "Default")
      (node (ref "R139") (pin "2") (pinfunction "2_2") (pintype "passive"))
      (node (ref "TP45") (pin "1") (pinfunction "1_1") (pintype "passive"))
    )
    (net (code "22") (name "/M.2_SAI0_RXD") (class "Default")
      (node (ref "J13") (pin "12") (pinfunction "I2S_SD_IN_12") (pintype "passive"))
      (node (ref "R138") (pin "2") (pinfunction "2_2") (pintype "passive"))
    )
    (net (code "23") (name "/M.2_SAI0_TXC") (class "Default")
      (node (ref "J13") (pin "8") (pinfunction "I2S_SCK_8") (pintype "passive"))
      (node (ref "R140") (pin "2") (pinfunction "2_2") (pintype "passive"))
    )
    (net (code "24") (name "/M.2_SAI0_TXD") (class "Default")
      (node (ref "J13") (pin "14") (pinfunction "I2S_SD_OUT_14") (pintype "passive"))
      (node (ref "R141") (pin "2") (pinfunction "2_2") (pintype "passive"))
    )
    (net (code "25") (name "/M.2_SAI0_TXFS") (class "Default")
      (node (ref "J13") (pin "10") (pinfunction "I2S_WS_10") (pintype "passive"))
      (node (ref "R142") (pin "2") (pinfunction "2_2") (pintype "passive"))
    )
    (net (code "26") (name "/M.2_USB_DN") (class "Default")
      (node (ref "J13") (pin "5") (pinfunction "USB_D-_5") (pintype "passive+no_connect"))
    )
    (net (code "27") (name "/M.2_USB_DP") (class "Default")
      (node (ref "J13") (pin "3") (pinfunction "USB_D+_3") (pintype "passive+no_connect"))
    )
    (net (code "28") (name "/M.2_WIFI_EN") (class "Default")
      (node (ref "J13") (pin "23") (pinfunction "SDIO_RST_23") (pintype "passive"))
      (node (ref "R146") (pin "1") (pinfunction "1_1") (pintype "passive"))
      (node (ref "U10") (pin "5") (pinfunction "A4_5") (pintype "passive"))
    )
    (net (code "29") (name "/M.2_WIFI_WAKE_B") (class "Default")
      (node (ref "J13") (pin "21") (pinfunction "SDIO_WAKE_21") (pintype "passive"))
      (node (ref "R147") (pin "1") (pinfunction "1_1") (pintype "passive"))
      (node (ref "U10") (pin "4") (pinfunction "A3_4") (pintype "passive"))
    )
    (net (code "30") (name "/M2_CLKREQ_B") (class "Default")
      (node (ref "R155") (pin "1") (pinfunction "1_1") (pintype "passive"))
      (node (ref "R169") (pin "1") (pinfunction "1_1") (pintype "passive"))
      (node (ref "U15") (pin "2") (pinfunction "B_2") (pintype "passive"))
    )
    (net (code "31") (name "/MICRO_REFCLK_N") (class "Default")
      (node (ref "U11") (pin "6") (pinfunction "C0_N_6") (pintype "passive"))
      (node (ref "U13") (pin "6") (pinfunction "C0_N_6") (pintype "passive"))
    )
    (net (code "32") (name "/MICRO_REFCLK_P") (class "Default")
      (node (ref "U11") (pin "5") (pinfunction "C0_P_5") (pintype "passive"))
      (node (ref "U13") (pin "5") (pinfunction "C0_P_5") (pintype "passive"))
    )
    (net (code "33") (name "/PCIE0_REF_CLK_N") (class "Default")
      (node (ref "R137") (pin "2") (pinfunction "2_2") (pintype "passive"))
      (node (ref "U11") (pin "9") (pinfunction "A0_N_9") (pintype "passive"))
    )
    (net (code "34") (name "/PCIE0_REF_CLK_P") (class "Default")
      (node (ref "R136") (pin "2") (pinfunction "2_2") (pintype "passive"))
      (node (ref "U11") (pin "10") (pinfunction "A0_P_10") (pintype "passive"))
    )
    (net (code "35") (name "/PCIE0_RX_N") (class "Default")
      (node (ref "R152") (pin "1") (pinfunction "1_1") (pintype "passive"))
    )
    (net (code "36") (name "/PCIE0_RX_P") (class "Default")
      (node (ref "R151") (pin "1") (pinfunction "1_1") (pintype "passive"))
    )
    (net (code "37") (name "/PCIE0_TX_N") (class "Default")
      (node (ref "C283") (pin "2") (pinfunction "2_2") (pintype "passive"))
    )
    (net (code "38") (name "/PCIE0_TX_P") (class "Default")
      (node (ref "C282") (pin "2") (pinfunction "2_2") (pintype "passive"))
    )
    (net (code "39") (name "/PCIE_CLK_SEL") (class "Default")
      (node (ref "R154") (pin "2") (pinfunction "2_2") (pintype "passive"))
      (node (ref "U11") (pin "12") (pinfunction "SEL_12") (pintype "passive"))
      (node (ref "U13") (pin "12") (pinfunction "SEL_12") (pintype "passive"))
    )
    (net (code "40") (name "/PCIE_CONN_REFCLK_N") (class "Default")
      (node (ref "J13") (pin "49") (pinfunction "REFCLK_N0_49") (pintype "passive"))
      (node (ref "R157") (pin "2") (pinfunction "2_2") (pintype "passive"))
      (node (ref "U13") (pin "9") (pinfunction "A0_N_9") (pintype "passive"))
    )
    (net (code "41") (name "/PCIE_CONN_REFCLK_P") (class "Default")
      (node (ref "J13") (pin "47") (pinfunction "REFCLK_P0_47") (pintype "passive"))
      (node (ref "R156") (pin "2") (pinfunction "2_2") (pintype "passive"))
      (node (ref "U13") (pin "10") (pinfunction "A0_P_10") (pintype "passive"))
    )
    (net (code "42") (name "/PCIE_CTRL_CLKREQ_B") (class "Default")
      (node (ref "R168") (pin "1") (pinfunction "1_1") (pintype "passive"))
      (node (ref "U15") (pin "1") (pinfunction "A_1") (pintype "passive"))
    )
    (net (code "43") (name "/PCIE_CTRL_PERST_B") (class "Default")
      (node (ref "R153") (pin "1") (pinfunction "1_1") (pintype "passive"))
    )
    (net (code "44") (name "/PCIE_CTRL_WAKE_B") (class "Default")
      (node (ref "J13") (pin "55") (pinfunction "PEWAKE0_55") (pintype "passive"))
      (node (ref "R150") (pin "1") (pinfunction "1_1") (pintype "passive"))
    )
    (net (code "45") (name "/PCIE_REF_CLK_N") (class "Default")
      (node (ref "R137") (pin "1") (pinfunction "1_1") (pintype "passive"))
    )
    (net (code "46") (name "/PCIE_REF_CLK_P") (class "Default")
      (node (ref "R136") (pin "1") (pinfunction "1_1") (pintype "passive"))
    )
    (net (code "47") (name "/PCI_CLKREQ") (class "Default")
      (node (ref "R163") (pin "2") (pinfunction "2_2") (pintype "passive"))
      (node (ref "R166") (pin "1") (pinfunction "1_1") (pintype "passive"))
      (node (ref "R167") (pin "1") (pinfunction "1_1") (pintype "passive"))
      (node (ref "R167") (pin "2") (pinfunction "2_2") (pintype "passive"))
      (node (ref "U12") (pin "22") (pinfunction "CKPWRGD_PD#_22") (pintype "passive"))
      (node (ref "U15") (pin "4") (pinfunction "Y_4") (pintype "passive"))
    )
    (net (code "48") (name "/PCI_XTAL_X1") (class "Default")
      (node (ref "C294") (pin "2") (pinfunction "2_2") (pintype "passive"))
      (node (ref "U12") (pin "1") (pinfunction "X1_25_1") (pintype "passive"))
      (node (ref "Y5") (pin "1") (pinfunction "IN_1") (pintype "passive"))
    )
    (net (code "49") (name "/PCI_XTAL_X2") (class "Default")
      (node (ref "R160") (pin "2") (pinfunction "2_2") (pintype "passive"))
      (node (ref "U12") (pin "2") (pinfunction "X2_2") (pintype "passive"))
    )
    (net (code "50") (name "/REFCLK1_N") (class "Default")
      (node (ref "R159") (pin "2") (pinfunction "2_2") (pintype "passive"))
      (node (ref "U11") (pin "7") (pinfunction "B0_N_7") (pintype "passive"))
    )
    (net (code "51") (name "/REFCLK1_P") (class "Default")
      (node (ref "R158") (pin "2") (pinfunction "2_2") (pintype "passive"))
      (node (ref "U11") (pin "8") (pinfunction "B0_P_8") (pintype "passive"))
    )
    (net (code "52") (name "/REFCLK2_N") (class "Default")
      (node (ref "R162") (pin "2") (pinfunction "2_2") (pintype "passive"))
      (node (ref "U13") (pin "7") (pinfunction "B0_N_7") (pintype "passive"))
    )
    (net (code "53") (name "/REFCLK2_P") (class "Default")
      (node (ref "R161") (pin "2") (pinfunction "2_2") (pintype "passive"))
      (node (ref "U13") (pin "8") (pinfunction "B0_P_8") (pintype "passive"))
    )
    (net (code "54") (name "/SPI0_CS0") (class "Default")
      (node (ref "R138") (pin "1") (pinfunction "1_1") (pintype "passive"))
    )
    (net (code "55") (name "/SPI0_CS1") (class "Default")
      (node (ref "R139") (pin "1") (pinfunction "1_1") (pintype "passive"))
    )
    (net (code "56") (name "/SPI0_SCK") (class "Default")
      (node (ref "R140") (pin "1") (pinfunction "1_1") (pintype "passive"))
    )
    (net (code "57") (name "/SPI0_SDI") (class "Default")
      (node (ref "R141") (pin "1") (pinfunction "1_1") (pintype "passive"))
    )
    (net (code "58") (name "/SPI0_SDO") (class "Default")
      (node (ref "R142") (pin "1") (pinfunction "1_1") (pintype "passive"))
    )
    (net (code "59") (name "/SS_CNTRL") (class "Default")
      (node (ref "U14") (pin "2") (pinfunction "A_2") (pintype "passive"))
    )
    (net (code "60") (name "/SS_CNTRL_B") (class "Default")
      (node (ref "U14") (pin "4") (pinfunction "Y_4") (pintype "passive"))
      (node (ref "U16") (pin "4") (pinfunction "B_4") (pintype "passive"))
    )
    (net (code "61") (name "/SS_EN_TRI") (class "Default")
      (node (ref "U12") (pin "23") (pinfunction "SS_EN_TRI_23") (pintype "passive"))
      (node (ref "U16") (pin "3") (pinfunction "A_3") (pintype "passive"))
    )
    (net (code "62") (name "/UART1_CTS_B") (class "Default")
      (node (ref "J13") (pin "34") (pinfunction "UART_CTS_34") (pintype "passive+no_connect"))
    )
    (net (code "63") (name "/UART1_RTS_B") (class "Default")
      (node (ref "J13") (pin "36") (pinfunction "UART_RTS_36") (pintype "passive+no_connect"))
    )
    (net (code "64") (name "/UART1_RX") (class "Default")
      (node (ref "J13") (pin "22") (pinfunction "UART_RXD_22") (pintype "passive+no_connect"))
    )
    (net (code "65") (name "/UART1_TX") (class "Default")
      (node (ref "J13") (pin "32") (pinfunction "UART_TXD_32") (pintype "passive+no_connect"))
    )
    (net (code "66") (name "/WIFI_DIS_B") (class "Default")
      (node (ref "J13") (pin "56") (pinfunction "W_DISABLE1_56") (pintype "passive"))
    )
    (net (code "67") (name "/WIFI_EN") (class "Default")
      (node (ref "U10") (pin "10") (pinfunction "B4_10") (pintype "passive"))
    )
    (net (code "68") (name "/WIFI_WAKE_B") (class "Default")
      (node (ref "U10") (pin "11") (pinfunction "B3_11") (pintype "passive"))
    )
    (net (code "69") (name "/XTAL2") (class "Default")
      (node (ref "C295") (pin "2") (pinfunction "2_2") (pintype "passive"))
      (node (ref "R160") (pin "1") (pinfunction "1_1") (pintype "passive"))
      (node (ref "Y5") (pin "3") (pinfunction "OUT_3") (pintype "passive"))
    )
    (net (code "75") (name "1V8") (class "Default")
      (node (ref "C280") (pin "2") (pinfunction "2_2") (pintype "passive"))
      (node (ref "C284") (pin "2") (pinfunction "2_2") (pintype "passive"))
      (node (ref "C285") (pin "2") (pinfunction "2_2") (pintype "passive"))
      (node (ref "C298") (pin "1") (pinfunction "1_1") (pintype "passive"))
      (node (ref "FB4") (pin "2") (pinfunction "2_2") (pintype "passive"))
      (node (ref "FB5") (pin "1") (pinfunction "1_1") (pintype "passive"))
      (node (ref "R145") (pin "2") (pinfunction "2_2") (pintype "passive"))
      (node (ref "R146") (pin "2") (pinfunction "2_2") (pintype "passive"))
      (node (ref "R147") (pin "2") (pinfunction "2_2") (pintype "passive"))
      (node (ref "R148") (pin "2") (pinfunction "2_2") (pintype "passive"))
      (node (ref "R149") (pin "2") (pinfunction "2_2") (pintype "passive"))
      (node (ref "R166") (pin "2") (pinfunction "2_2") (pintype "passive"))
      (node (ref "U10") (pin "1") (pinfunction "VCCA_1") (pintype "power_in"))
      (node (ref "U12") (pin "7") (pinfunction "VDDDIG1.8_7") (pintype "passive"))
      (node (ref "U16") (pin "1") (pinfunction "VCCA_1") (pintype "passive"))
    )
    (net (code "76") (name "3V3") (class "Default")
      (node (ref "C275") (pin "2") (pinfunction "2_2") (pintype "passive"))
      (node (ref "C276") (pin "2") (pinfunction "2_2") (pintype "passive"))
      (node (ref "C277") (pin "2") (pinfunction "2_2") (pintype "passive"))
      (node (ref "C278") (pin "2") (pinfunction "2_2") (pintype "passive"))
      (node (ref "C279") (pin "2") (pinfunction "2_2") (pintype "passive"))
      (node (ref "C281") (pin "2") (pinfunction "2_2") (pintype "passive"))
      (node (ref "C292") (pin "2") (pinfunction "2_2") (pintype "passive"))
      (node (ref "C293") (pin "2") (pinfunction "2_2") (pintype "passive"))
      (node (ref "C296") (pin "1") (pinfunction "1_1") (pintype "passive"))
      (node (ref "C297") (pin "1") (pinfunction "1_1") (pintype "passive"))
      (node (ref "C299") (pin "1") (pinfunction "1_1") (pintype "passive"))
      (node (ref "J13") (pin "2") (pinfunction "3V3_1_2") (pintype "passive"))
      (node (ref "J13") (pin "4") (pinfunction "3V3_2_4") (pintype "passive"))
      (node (ref "J13") (pin "72") (pinfunction "3V3_3_72") (pintype "passive"))
      (node (ref "J13") (pin "74") (pinfunction "3V3_4_74") (pintype "passive"))
      (node (ref "R143") (pin "2") (pinfunction "2_2") (pintype "passive"))
      (node (ref "R144") (pin "2") (pinfunction "2_2") (pintype "passive"))
      (node (ref "R150") (pin "2") (pinfunction "2_2") (pintype "passive"))
      (node (ref "R154") (pin "1") (pinfunction "1_1") (pintype "passive"))
      (node (ref "R168") (pin "2") (pinfunction "2_2") (pintype "passive"))
      (node (ref "R169") (pin "2") (pinfunction "2_2") (pintype "passive"))
      (node (ref "U10") (pin "14") (pinfunction "VCCB_14") (pintype "power_in"))
      (node (ref "U11") (pin "4") (pinfunction "VDD_4") (pintype "power_in"))
      (node (ref "U13") (pin "4") (pinfunction "VDD_4") (pintype "power_in"))
      (node (ref "U14") (pin "5") (pinfunction "VCC_5") (pintype "power_in"))
      (node (ref "U15") (pin "5") (pinfunction "VCC_5") (pintype "passive"))
      (node (ref "U16") (pin "6") (pinfunction "VCCB_6") (pintype "passive"))
      (node (ref "Y4") (pin "3") (pinfunction "OE_3") (pintype "passive"))
      (node (ref "Y4") (pin "4") (pinfunction "VDD_4") (pintype "passive"))
    )
    (net (code "77") (name "GND") (class "Default")
      (node (ref "C275") (pin "1") (pinfunction "1_1") (pintype "passive"))
      (node (ref "C276") (pin "1") (pinfunction "1_1") (pintype "passive"))
      (node (ref "C277") (pin "1") (pinfunction "1_1") (pintype "passive"))
      (node (ref "C278") (pin "1") (pinfunction "1_1") (pintype "passive"))
      (node (ref "C279") (pin "1") (pinfunction "1_1") (pintype "passive"))
      (node (ref "C280") (pin "1") (pinfunction "1_1") (pintype "passive"))
      (node (ref "C281") (pin "1") (pinfunction "1_1") (pintype "passive"))
      (node (ref "C284") (pin "1") (pinfunction "1_1") (pintype "passive"))
      (node (ref "C285") (pin "1") (pinfunction "1_1") (pintype "passive"))
      (node (ref "C286") (pin "1") (pinfunction "1_1") (pintype "passive"))
      (node (ref "C287") (pin "1") (pinfunction "1_1") (pintype "passive"))
      (node (ref "C288") (pin "1") (pinfunction "1_1") (pintype "passive"))
      (node (ref "C289") (pin "1") (pinfunction "1_1") (pintype "passive"))
      (node (ref "C290") (pin "1") (pinfunction "1_1") (pintype "passive"))
      (node (ref "C291") (pin "1") (pinfunction "1_1") (pintype "passive"))
      (node (ref "C292") (pin "1") (pinfunction "1_1") (pintype "passive"))
      (node (ref "C293") (pin "1") (pinfunction "1_1") (pintype "passive"))
      (node (ref "C294") (pin "1") (pinfunction "1_1") (pintype "passive"))
      (node (ref "C295") (pin "1") (pinfunction "1_1") (pintype "passive"))
      (node (ref "C296") (pin "2") (pinfunction "2_2") (pintype "passive"))
      (node (ref "C297") (pin "2") (pinfunction "2_2") (pintype "passive"))
      (node (ref "C298") (pin "2") (pinfunction "2_2") (pintype "passive"))
      (node (ref "C299") (pin "2") (pinfunction "2_2") (pintype "passive"))
      (node (ref "J13") (pin "1") (pinfunction "GND1_1") (pintype "passive"))
      (node (ref "J13") (pin "18") (pinfunction "GND3_18") (pintype "passive"))
      (node (ref "J13") (pin "33") (pinfunction "GND5_33") (pintype "passive"))
      (node (ref "J13") (pin "39") (pinfunction "GND4_39") (pintype "passive"))
      (node (ref "J13") (pin "45") (pinfunction "GND6_45") (pintype "passive"))
      (node (ref "J13") (pin "51") (pinfunction "GND7_51") (pintype "passive"))
      (node (ref "J13") (pin "57") (pinfunction "GND8_57") (pintype "passive"))
      (node (ref "J13") (pin "63") (pinfunction "GND9_63") (pintype "passive"))
      (node (ref "J13") (pin "69") (pinfunction "GND10_69") (pintype "passive"))
      (node (ref "J13") (pin "7") (pinfunction "GND2_7") (pintype "passive"))
      (node (ref "J13") (pin "75") (pinfunction "GND11_75") (pintype "passive"))
      (node (ref "J13") (pin "S1") (pinfunction "SHIELD_S1") (pintype "passive"))
      (node (ref "J13") (pin "S2") (pinfunction "SHIELD_S2") (pintype "passive"))
      (node (ref "R156") (pin "1") (pinfunction "1_1") (pintype "passive"))
      (node (ref "R157") (pin "1") (pinfunction "1_1") (pintype "passive"))
      (node (ref "R163") (pin "1") (pinfunction "1_1") (pintype "passive"))
      (node (ref "R164") (pin "1") (pinfunction "1_1") (pintype "passive"))
      (node (ref "R165") (pin "1") (pinfunction "1_1") (pintype "passive"))
      (node (ref "R170") (pin "2") (pinfunction "2_2") (pintype "passive"))
      (node (ref "U10") (pin "6") (pinfunction "NC_6") (pintype "passive"))
      (node (ref "U10") (pin "9") (pinfunction "NC_9") (pintype "passive"))
      (node (ref "U11") (pin "11") (pinfunction "VSS_11") (pintype "power_in"))
      (node (ref "U11") (pin "13") (pinfunction "A1_P_13") (pintype "passive"))
      (node (ref "U11") (pin "14") (pinfunction "A1_N_14") (pintype "passive"))
      (node (ref "U11") (pin "17") (pinfunction "EPAD_17") (pintype "power_in"))
      (node (ref "U11") (pin "3") (pinfunction "XSD_3") (pintype "passive"))
      (node (ref "U12") (pin "10") (pinfunction "GND_1_10") (pintype "passive"))
      (node (ref "U12") (pin "15") (pinfunction "GNDA_15") (pintype "passive"))
      (node (ref "U12") (pin "21") (pinfunction "GND_2_21") (pintype "passive"))
      (node (ref "U12") (pin "24") (pinfunction "GNDXTAL_24") (pintype "passive"))
      (node (ref "U12") (pin "25") (pinfunction "GND_3_25") (pintype "passive"))
      (node (ref "U12") (pin "5") (pinfunction "GNDREF_5") (pintype "passive"))
      (node (ref "U12") (pin "6") (pinfunction "GNDDIG_6") (pintype "passive"))
      (node (ref "U13") (pin "11") (pinfunction "VSS_11") (pintype "power_in"))
      (node (ref "U13") (pin "13") (pinfunction "A1_P_13") (pintype "passive"))
      (node (ref "U13") (pin "14") (pinfunction "A1_N_14") (pintype "passive"))
      (node (ref "U13") (pin "17") (pinfunction "EPAD_17") (pintype "power_in"))
      (node (ref "U13") (pin "3") (pinfunction "XSD_3") (pintype "passive"))
      (node (ref "U14") (pin "1") (pinfunction "NC_1") (pintype "passive"))
      (node (ref "U14") (pin "3") (pinfunction "GND_3") (pintype "power_in"))
      (node (ref "U15") (pin "3") (pinfunction "GND_3") (pintype "passive"))
      (node (ref "U16") (pin "2") (pinfunction "GND_2") (pintype "passive"))
      (node (ref "Y4") (pin "2") (pinfunction "GND_2") (pintype "passive"))
      (node (ref "Y5") (pin "2") (pinfunction "2_2") (pintype "passive"))
      (node (ref "Y5") (pin "4") (pinfunction "4_4") (pintype "passive"))
    )
    (net (code "78") (name "Net-(D10-A)") (class "Default")
      (node (ref "D10") (pin "2") (pinfunction "A_2") (pintype "passive"))
      (node (ref "R143") (pin "1") (pinfunction "1_1") (pintype "passive"))
    )
    (net (code "79") (name "Net-(D11-A)") (class "Default")
      (node (ref "D11") (pin "2") (pinfunction "A_2") (pintype "passive"))
      (node (ref "R144") (pin "1") (pinfunction "1_1") (pintype "passive"))
    )
    (net (code "80") (name "Net-(J13-CLKREQ0)") (class "Default")
      (node (ref "J13") (pin "53") (pinfunction "CLKREQ0_53") (pintype "passive"))
      (node (ref "R155") (pin "2") (pinfunction "2_2") (pintype "passive"))
    )
    (net (code "81") (name "Net-(J13-PERST0)") (class "Default")
      (node (ref "J13") (pin "52") (pinfunction "PERST0_52") (pintype "passive"))
      (node (ref "R153") (pin "2") (pinfunction "2_2") (pintype "passive"))
    )
    (net (code "82") (name "Net-(U10-OE)") (class "Default")
      (node (ref "R145") (pin "1") (pinfunction "1_1") (pintype "passive"))
      (node (ref "U10") (pin "8") (pinfunction "OE_8") (pintype "passive"))
    )
    (net (code "83") (name "Net-(U12-DIF0#)") (class "Default")
      (node (ref "R162") (pin "1") (pinfunction "1_1") (pintype "passive"))
      (node (ref "U12") (pin "14") (pinfunction "DIF0#_14") (pintype "passive"))
    )
    (net (code "84") (name "Net-(U12-DIF0)") (class "Default")
      (node (ref "R161") (pin "1") (pinfunction "1_1") (pintype "passive"))
      (node (ref "U12") (pin "13") (pinfunction "DIF0_13") (pintype "passive"))
    )
    (net (code "85") (name "Net-(U12-DIF1#)") (class "Default")
      (node (ref "R159") (pin "1") (pinfunction "1_1") (pintype "passive"))
      (node (ref "U12") (pin "18") (pinfunction "DIF1#_18") (pintype "passive"))
    )
    (net (code "86") (name "Net-(U12-DIF1)") (class "Default")
      (node (ref "R158") (pin "1") (pinfunction "1_1") (pintype "passive"))
      (node (ref "U12") (pin "17") (pinfunction "DIF1_17") (pintype "passive"))
    )
    (net (code "87") (name "Net-(U12-OE0#)") (class "Default")
      (node (ref "R164") (pin "2") (pinfunction "2_2") (pintype "passive"))
      (node (ref "U12") (pin "12") (pinfunction "OE0#_12") (pintype "passive"))
    )
    (net (code "88") (name "Net-(U12-OE1#)") (class "Default")
      (node (ref "R165") (pin "2") (pinfunction "2_2") (pintype "passive"))
      (node (ref "U12") (pin "19") (pinfunction "OE1#_19") (pintype "passive"))
    )
    (net (code "89") (name "Net-(U12-SADR{slash}REF1.8)") (class "Default")
      (node (ref "TP46") (pin "1") (pinfunction "1_1") (pintype "passive"))
      (node (ref "U12") (pin "4") (pinfunction "SADR/REF1.8_4") (pintype "passive"))
    )
    (net (code "90") (name "Net-(U12-VDD1.8_1)") (class "Default")
      (node (ref "C289") (pin "2") (pinfunction "2_2") (pintype "passive"))
      (node (ref "C290") (pin "2") (pinfunction "2_2") (pintype "passive"))
      (node (ref "C291") (pin "2") (pinfunction "2_2") (pintype "passive"))
      (node (ref "FB5") (pin "2") (pinfunction "2_2") (pintype "passive"))
      (node (ref "U12") (pin "11") (pinfunction "VDD1.8_1_11") (pintype "passive"))
      (node (ref "U12") (pin "20") (pinfunction "VDD1.8_2_20") (pintype "passive"))
    )
    (net (code "91") (name "Net-(U12-VDDA1.8)") (class "Default")
      (node (ref "C286") (pin "2") (pinfunction "2_2") (pintype "passive"))
      (node (ref "C287") (pin "2") (pinfunction "2_2") (pintype "passive"))
      (node (ref "C288") (pin "2") (pinfunction "2_2") (pintype "passive"))
      (node (ref "FB4") (pin "1") (pinfunction "1_1") (pintype "passive"))
      (node (ref "U12") (pin "16") (pinfunction "VDDA1.8_16") (pintype "passive"))
      (node (ref "U12") (pin "3") (pinfunction "VDDXTAL1.8_3") (pintype "passive"))
    )
    (net (code "92") (name "Net-(U16-DIR)") (class "Default")
      (node (ref "R170") (pin "1") (pinfunction "1_1") (pintype "passive"))
      (node (ref "U16") (pin "5") (pinfunction "DIR_5") (pintype "passive"))
    )
    (net (code "93") (name "unconnected-(J13-ALERT-Pad62)") (class "Default")
      (node (ref "J13") (pin "62") (pinfunction "ALERT_62") (pintype "passive+no_connect"))
    )
    (net (code "94") (name "unconnected-(J13-CLKREQ1-Pad68)") (class "Default")
      (node (ref "J13") (pin "68") (pinfunction "CLKREQ1_68") (pintype "passive+no_connect"))
    )
    (net (code "95") (name "unconnected-(J13-COEX1-Pad48)") (class "Default")
      (node (ref "J13") (pin "48") (pinfunction "COEX1_48") (pintype "passive+no_connect"))
    )
    (net (code "96") (name "unconnected-(J13-COEX2-Pad46)") (class "Default")
      (node (ref "J13") (pin "46") (pinfunction "COEX2_46") (pintype "passive+no_connect"))
    )
    (net (code "97") (name "unconnected-(J13-COEX3-Pad44)") (class "Default")
      (node (ref "J13") (pin "44") (pinfunction "COEX3_44") (pintype "passive+no_connect"))
    )
    (net (code "98") (name "unconnected-(J13-PERST1-Pad66)") (class "Default")
      (node (ref "J13") (pin "66") (pinfunction "PERST1_66") (pintype "passive+no_connect"))
    )
    (net (code "99") (name "unconnected-(J13-PER_N1-Pad67)") (class "Default")
      (node (ref "J13") (pin "67") (pinfunction "PER_N1_67") (pintype "passive+no_connect"))
    )
    (net (code "100") (name "unconnected-(J13-PER_P1-Pad65)") (class "Default")
      (node (ref "J13") (pin "65") (pinfunction "PER_P1_65") (pintype "passive+no_connect"))
    )
    (net (code "101") (name "unconnected-(J13-PET_N1-Pad61)") (class "Default")
      (node (ref "J13") (pin "61") (pinfunction "PET_N1_61") (pintype "passive+no_connect"))
    )
    (net (code "102") (name "unconnected-(J13-PET_P1-Pad59)") (class "Default")
      (node (ref "J13") (pin "59") (pinfunction "PET_P1_59") (pintype "passive+no_connect"))
    )
    (net (code "103") (name "unconnected-(J13-PEWAKE1-Pad70)") (class "Default")
      (node (ref "J13") (pin "70") (pinfunction "PEWAKE1_70") (pintype "passive+no_connect"))
    )
    (net (code "104") (name "unconnected-(J13-REFCLK_N1-Pad73)") (class "Default")
      (node (ref "J13") (pin "73") (pinfunction "REFCLK_N1_73") (pintype "passive+no_connect"))
    )
    (net (code "105") (name "unconnected-(J13-REFCLK_P1-Pad71)") (class "Default")
      (node (ref "J13") (pin "71") (pinfunction "REFCLK_P1_71") (pintype "passive+no_connect"))
    )
    (net (code "106") (name "unconnected-(J13-RESERVED-Pad64)") (class "Default")
      (node (ref "J13") (pin "64") (pinfunction "RESERVED_64") (pintype "passive+no_connect"))
    )
    (net (code "107") (name "unconnected-(J13-SDIO_CLK-Pad9)") (class "Default")
      (node (ref "J13") (pin "9") (pinfunction "SDIO_CLK_9") (pintype "passive+no_connect"))
    )
    (net (code "108") (name "unconnected-(J13-SDIO_CMD-Pad11)") (class "Default")
      (node (ref "J13") (pin "11") (pinfunction "SDIO_CMD_11") (pintype "passive+no_connect"))
    )
    (net (code "109") (name "unconnected-(J13-SDIO_DATA0-Pad13)") (class "Default")
      (node (ref "J13") (pin "13") (pinfunction "SDIO_DATA0_13") (pintype "passive+no_connect"))
    )
    (net (code "110") (name "unconnected-(J13-SDIO_DATA1-Pad15)") (class "Default")
      (node (ref "J13") (pin "15") (pinfunction "SDIO_DATA1_15") (pintype "passive+no_connect"))
    )
    (net (code "111") (name "unconnected-(J13-SDIO_DATA2-Pad17)") (class "Default")
      (node (ref "J13") (pin "17") (pinfunction "SDIO_DATA2_17") (pintype "passive+no_connect"))
    )
    (net (code "112") (name "unconnected-(J13-SDIO_DATA3-Pad19)") (class "Default")
      (node (ref "J13") (pin "19") (pinfunction "SDIO_DATA3_19") (pintype "passive+no_connect"))
    )
    (net (code "113") (name "unconnected-(J13-VEN_DEF1-Pad38)") (class "Default")
      (node (ref "J13") (pin "38") (pinfunction "VEN_DEF1_38") (pintype "passive+no_connect"))
    )
    (net (code "114") (name "unconnected-(J13-VEN_DEF2-Pad40)") (class "Default")
      (node (ref "J13") (pin "40") (pinfunction "VEN_DEF2_40") (pintype "passive+no_connect"))
    )
    (net (code "115") (name "unconnected-(J13-VEN_DEF3-Pad42)") (class "Default")
      (node (ref "J13") (pin "42") (pinfunction "VEN_DEF3_42") (pintype "passive+no_connect"))
    )
    (net (code "116") (name "unconnected-(U10-EP-Pad15)") (class "Default")
      (node (ref "U10") (pin "15") (pinfunction "EP_15") (pintype "passive+no_connect"))
    )
    (net (code "117") (name "unconnected-(U10-GND-Pad7)") (class "Default")
      (node (ref "U10") (pin "7") (pinfunction "GND_7") (pintype "power_in+no_connect"))
    )
    (net (code "118") (name "unconnected-(U11-B1_N-Pad1)") (class "Default")
      (node (ref "U11") (pin "1") (pinfunction "B1_N_1") (pintype "passive+no_connect"))
    )
    (net (code "119") (name "unconnected-(U11-B1_P-Pad2)") (class "Default")
      (node (ref "U11") (pin "2") (pinfunction "B1_P_2") (pintype "passive+no_connect"))
    )
    (net (code "120") (name "unconnected-(U11-C1_N-Pad16)") (class "Default")
      (node (ref "U11") (pin "16") (pinfunction "C1_N_16") (pintype "passive+no_connect"))
    )
    (net (code "121") (name "unconnected-(U11-C1_P-Pad15)") (class "Default")
      (node (ref "U11") (pin "15") (pinfunction "C1_P_15") (pintype "passive+no_connect"))
    )
    (net (code "122") (name "unconnected-(U13-B1_N-Pad1)") (class "Default")
      (node (ref "U13") (pin "1") (pinfunction "B1_N_1") (pintype "passive+no_connect"))
    )
    (net (code "123") (name "unconnected-(U13-B1_P-Pad2)") (class "Default")
      (node (ref "U13") (pin "2") (pinfunction "B1_P_2") (pintype "passive+no_connect"))
    )
    (net (code "124") (name "unconnected-(U13-C1_N-Pad16)") (class "Default")
      (node (ref "U13") (pin "16") (pinfunction "C1_N_16") (pintype "passive+no_connect"))
    )
    (net (code "125") (name "unconnected-(U13-C1_P-Pad15)") (class "Default")
      (node (ref "U13") (pin "15") (pinfunction "C1_P_15") (pintype "passive+no_connect"))
    )
  )
)
